# vending_machine.net
KiCad netlist of a schematic drawn in EAGLE
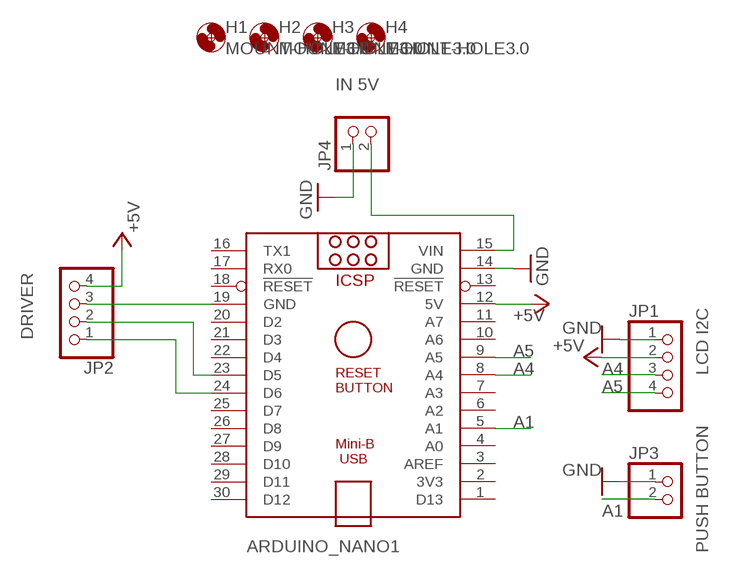
[diagram p0: schematic, sheet 1]

(export (version "E")
  (design (tool "Eeschema 10.0.6"))
  (components
    (comp (ref "ARDUINO_NANO1")
      (value "ARDUINO_NANO")
      (footprint "eagle-import:ARDUINO_NANO")
      (libsource (lib "eagle-import") (part "ARDUINO_NANO"))
    )
    (comp (ref "H1")
      (value "MOUNT-HOLE3.0")
      (footprint "eagle-import:3,0")
      (libsource (lib "eagle-import") (part "MOUNT-HOLE3.0"))
    )
    (comp (ref "H2")
      (value "MOUNT-HOLE3.0")
      (footprint "eagle-import:3,0")
      (libsource (lib "eagle-import") (part "MOUNT-HOLE3.0"))
    )
    (comp (ref "H3")
      (value "MOUNT-HOLE3.0")
      (footprint "eagle-import:3,0")
      (libsource (lib "eagle-import") (part "MOUNT-HOLE3.0"))
    )
    (comp (ref "H4")
      (value "MOUNT-HOLE3.0")
      (footprint "eagle-import:3,0")
      (libsource (lib "eagle-import") (part "MOUNT-HOLE3.0"))
    )
    (comp (ref "JP1")
      (value "PINHD-1X4")
      (footprint "eagle-import:1X04")
      (libsource (lib "eagle-import") (part "PINHD-1X4"))
    )
    (comp (ref "JP2")
      (value "PINHD-1X4")
      (footprint "eagle-import:1X04")
      (libsource (lib "eagle-import") (part "PINHD-1X4"))
    )
    (comp (ref "JP3")
      (value "PINHD-1X2")
      (footprint "eagle-import:1X02")
      (libsource (lib "eagle-import") (part "PINHD-1X2"))
    )
    (comp (ref "JP4")
      (value "PINHD-1X2")
      (footprint "eagle-import:1X02")
      (libsource (lib "eagle-import") (part "PINHD-1X2"))
    )
  )
  (nets
    (net (code "1") (name "+5V") (class "Default")
      (node (ref "ARDUINO_NANO1") (pin "12") (pinfunction "5V_12") (pintype "power_in"))
      (node (ref "JP1") (pin "2") (pinfunction "2_2") (pintype "passive"))
      (node (ref "JP2") (pin "4") (pinfunction "4_4") (pintype "passive"))
    )
    (net (code "2") (name "/A1") (class "Default")
      (node (ref "ARDUINO_NANO1") (pin "5") (pinfunction "A1_5") (pintype "bidirectional"))
      (node (ref "JP3") (pin "2") (pinfunction "2_2") (pintype "passive"))
    )
    (net (code "3") (name "/A4") (class "Default")
      (node (ref "ARDUINO_NANO1") (pin "8") (pinfunction "A4_8") (pintype "bidirectional"))
      (node (ref "JP1") (pin "3") (pinfunction "3_3") (pintype "passive"))
    )
    (net (code "4") (name "/A5") (class "Default")
      (node (ref "ARDUINO_NANO1") (pin "9") (pinfunction "A5_9") (pintype "bidirectional"))
      (node (ref "JP1") (pin "4") (pinfunction "4_4") (pintype "passive"))
    )
    (net (code "5") (name "GND") (class "Default")
      (node (ref "ARDUINO_NANO1") (pin "14") (pinfunction "GND_14") (pintype "power_in"))
      (node (ref "JP1") (pin "1") (pinfunction "1_1") (pintype "passive"))
      (node (ref "JP3") (pin "1") (pinfunction "1_1") (pintype "passive"))
      (node (ref "JP4") (pin "1") (pinfunction "1_1") (pintype "passive"))
    )
    (net (code "6") (name "Net-(ARDUINO_NANO1-D5)") (class "Default")
      (node (ref "ARDUINO_NANO1") (pin "23") (pinfunction "D5_23") (pintype "bidirectional"))
      (node (ref "JP2") (pin "2") (pinfunction "2_2") (pintype "passive"))
    )
    (net (code "7") (name "Net-(ARDUINO_NANO1-D6)") (class "Default")
      (node (ref "ARDUINO_NANO1") (pin "24") (pinfunction "D6_24") (pintype "bidirectional"))
      (node (ref "JP2") (pin "1") (pinfunction "1_1") (pintype "passive"))
    )
    (net (code "8") (name "Net-(ARDUINO_NANO1-GND-Pad19)") (class "Default")
      (node (ref "ARDUINO_NANO1") (pin "19") (pinfunction "GND_19") (pintype "power_in"))
      (node (ref "JP2") (pin "3") (pinfunction "3_3") (pintype "passive"))
    )
    (net (code "9") (name "Net-(ARDUINO_NANO1-VIN)") (class "Default")
      (node (ref "ARDUINO_NANO1") (pin "15") (pinfunction "VIN_15") (pintype "power_in"))
      (node (ref "JP4") (pin "2") (pinfunction "2_2") (pintype "passive"))
    )
    (net (code "10") (name "unconnected-(ARDUINO_NANO1-3V3-Pad2)") (class "Default")
      (node (ref "ARDUINO_NANO1") (pin "2") (pinfunction "3V3_2") (pintype "output"))
    )
    (net (code "11") (name "unconnected-(ARDUINO_NANO1-A0-Pad4)") (class "Default")
      (node (ref "ARDUINO_NANO1") (pin "4") (pinfunction "A0_4") (pintype "bidirectional"))
    )
    (net (code "12") (name "unconnected-(ARDUINO_NANO1-A2-Pad6)") (class "Default")
      (node (ref "ARDUINO_NANO1") (pin "6") (pinfunction "A2_6") (pintype "bidirectional"))
    )
    (net (code "13") (name "unconnected-(ARDUINO_NANO1-A3-Pad7)") (class "Default")
      (node (ref "ARDUINO_NANO1") (pin "7") (pinfunction "A3_7") (pintype "bidirectional"))
    )
    (net (code "14") (name "unconnected-(ARDUINO_NANO1-A6-Pad10)") (class "Default")
      (node (ref "ARDUINO_NANO1") (pin "10") (pinfunction "A6_10") (pintype "bidirectional"))
    )
    (net (code "15") (name "unconnected-(ARDUINO_NANO1-A7-Pad11)") (class "Default")
      (node (ref "ARDUINO_NANO1") (pin "11") (pinfunction "A7_11") (pintype "bidirectional"))
    )
    (net (code "16") (name "unconnected-(ARDUINO_NANO1-AREF-Pad3)") (class "Default")
      (node (ref "ARDUINO_NANO1") (pin "3") (pinfunction "AREF_3") (pintype "input"))
    )
    (net (code "17") (name "unconnected-(ARDUINO_NANO1-D2-Pad20)") (class "Default")
      (node (ref "ARDUINO_NANO1") (pin "20") (pinfunction "D2_20") (pintype "bidirectional"))
    )
    (net (code "18") (name "unconnected-(ARDUINO_NANO1-D3-Pad21)") (class "Default")
      (node (ref "ARDUINO_NANO1") (pin "21") (pinfunction "D3_21") (pintype "bidirectional"))
    )
    (net (code "19") (name "unconnected-(ARDUINO_NANO1-D4-Pad22)") (class "Default")
      (node (ref "ARDUINO_NANO1") (pin "22") (pinfunction "D4_22") (pintype "bidirectional"))
    )
    (net (code "20") (name "unconnected-(ARDUINO_NANO1-D7-Pad25)") (class "Default")
      (node (ref "ARDUINO_NANO1") (pin "25") (pinfunction "D7_25") (pintype "bidirectional"))
    )
    (net (code "21") (name "unconnected-(ARDUINO_NANO1-D8-Pad26)") (class "Default")
      (node (ref "ARDUINO_NANO1") (pin "26") (pinfunction "D8_26") (pintype "bidirectional"))
    )
    (net (code "22") (name "unconnected-(ARDUINO_NANO1-D9-Pad27)") (class "Default")
      (node (ref "ARDUINO_NANO1") (pin "27") (pinfunction "D9_27") (pintype "bidirectional"))
    )
    (net (code "23") (name "unconnected-(ARDUINO_NANO1-D10-Pad28)") (class "Default")
      (node (ref "ARDUINO_NANO1") (pin "28") (pinfunction "D10_28") (pintype "bidirectional"))
    )
    (net (code "24") (name "unconnected-(ARDUINO_NANO1-D11-Pad29)") (class "Default")
      (node (ref "ARDUINO_NANO1") (pin "29") (pinfunction "D11_29") (pintype "bidirectional"))
    )
    (net (code "25") (name "unconnected-(ARDUINO_NANO1-D12-Pad30)") (class "Default")
      (node (ref "ARDUINO_NANO1") (pin "30") (pinfunction "D12_30") (pintype "bidirectional"))
    )
    (net (code "26") (name "unconnected-(ARDUINO_NANO1-D13-Pad1)") (class "Default")
      (node (ref "ARDUINO_NANO1") (pin "1") (pinfunction "D13_1") (pintype "bidirectional"))
    )
    (net (code "27") (name "unconnected-(ARDUINO_NANO1-RX0-Pad17)") (class "Default")
      (node (ref "ARDUINO_NANO1") (pin "17") (pinfunction "RX0_17") (pintype "bidirectional"))
    )
    (net (code "28") (name "unconnected-(ARDUINO_NANO1-TX1-Pad16)") (class "Default")
      (node (ref "ARDUINO_NANO1") (pin "16") (pinfunction "TX1_16") (pintype "bidirectional"))
    )
    (net (code "29") (name "unconnected-(ARDUINO_NANO1-~{RESET}-Pad13)") (class "Default")
      (node (ref "ARDUINO_NANO1") (pin "13") (pinfunction "~{RESET}_13") (pintype "input"))
    )
    (net (code "30") (name "unconnected-(ARDUINO_NANO1-~{RESET}-Pad18)") (class "Default")
      (node (ref "ARDUINO_NANO1") (pin "18") (pinfunction "~{RESET}_18") (pintype "input"))
    )
  )
)
